# MIXR_Input_-_Instrument_Inputs.net
KiCad netlist of a schematic drawn in Altium Designer
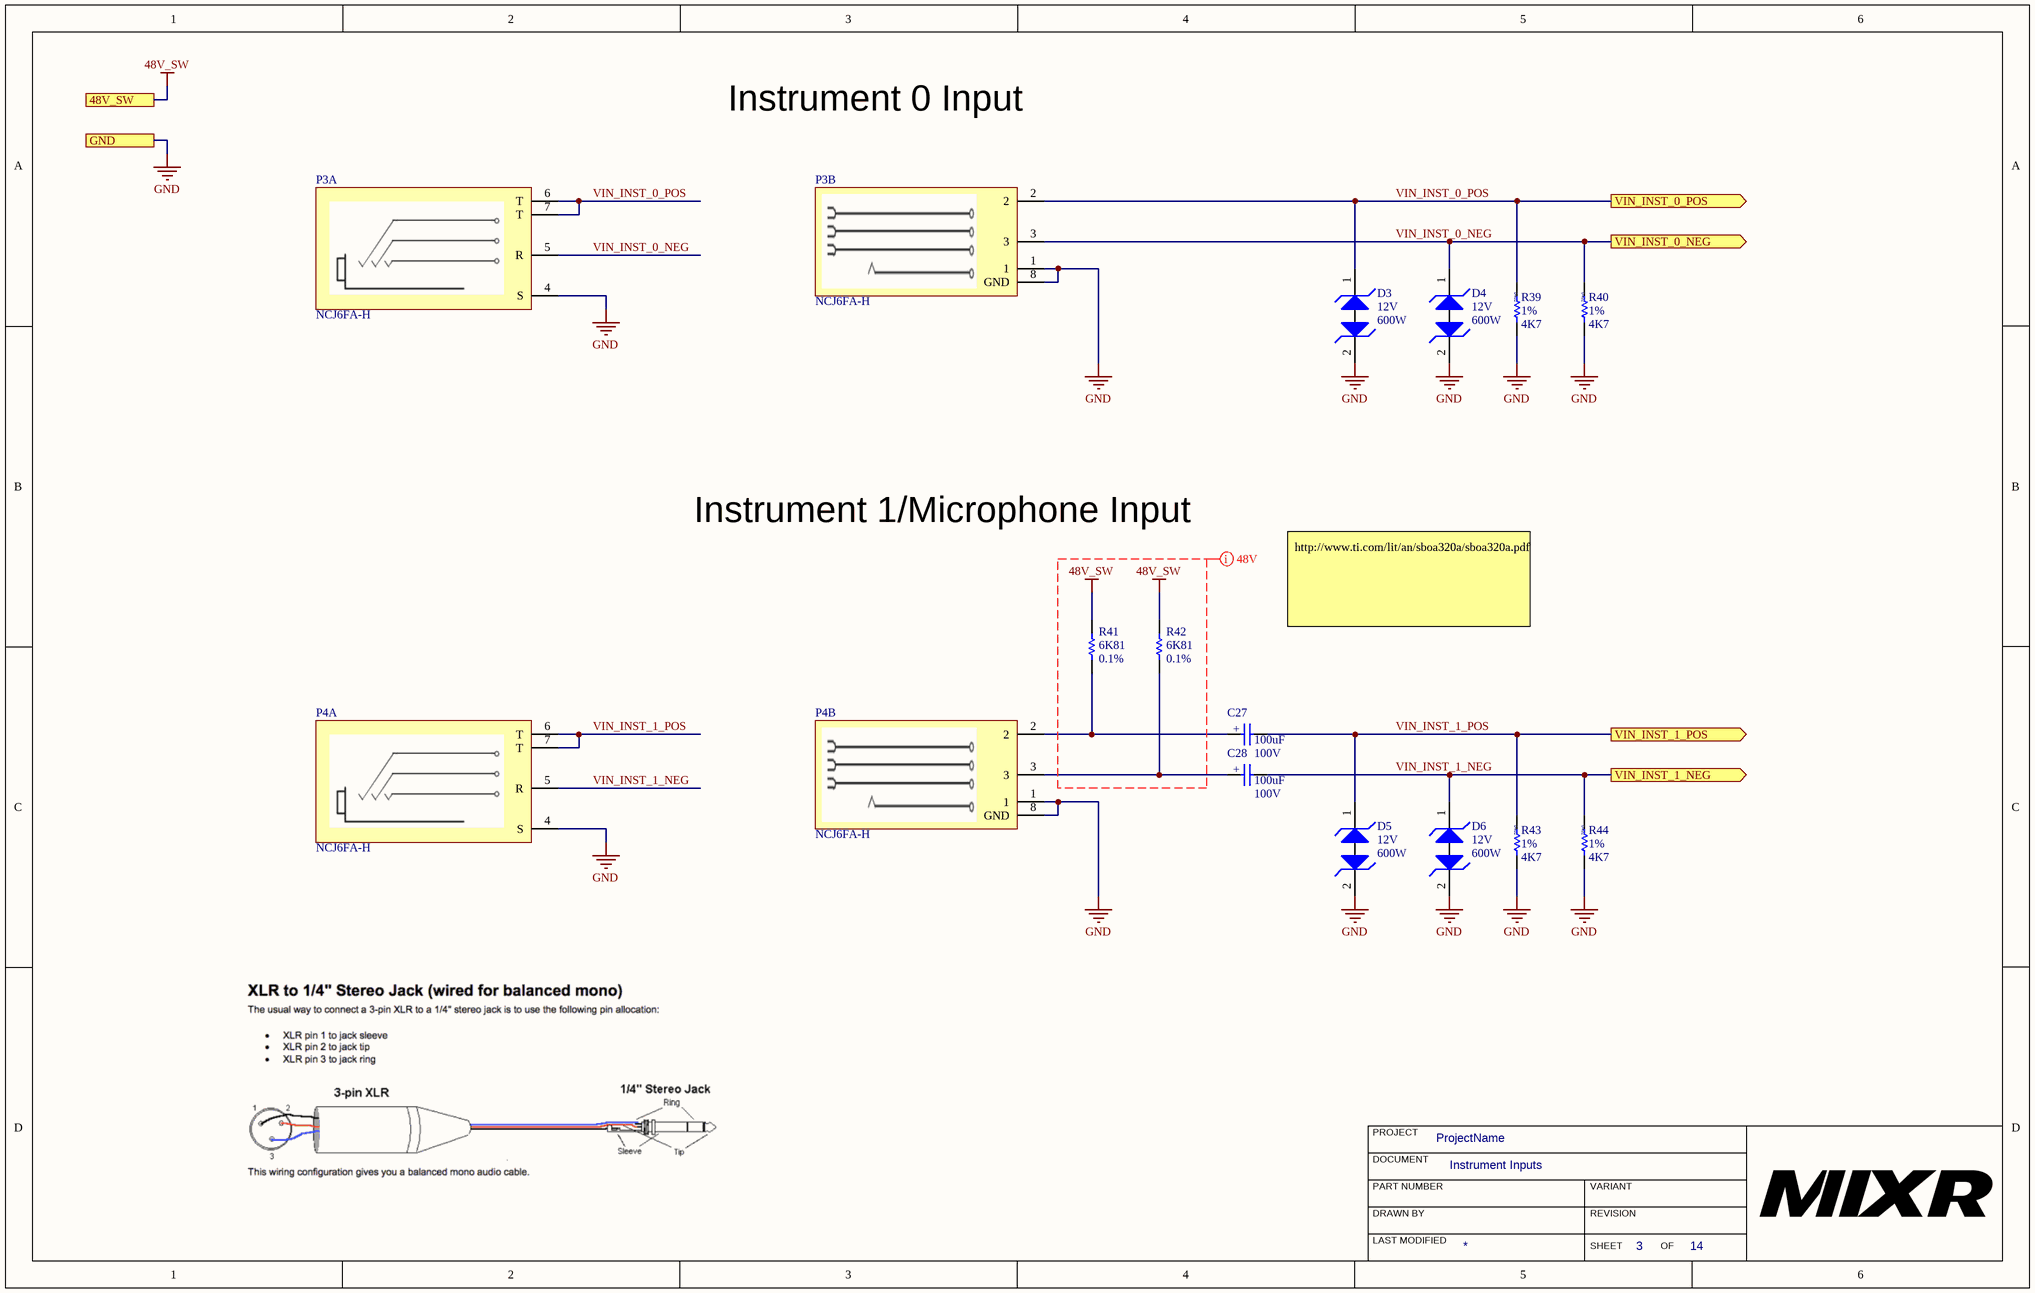
[diagram p0: MIXR Input - Instrument Inputs.SchDoc]

(export (version "E")
  (design (tool "Eeschema 10.0.6"))
  (components
    (comp (ref "C27")
      (value "CAP ALUM 100UF 20% 100V RADIAL")
      (footprint "CAP ALUM RADIAL 10x20")
      (fields
        (field (name "MANUFACTURER") "Nichicon")
        (field (name "MANUFACTURER PART NUMBER") "UFW2A101MPD1TD")
        (field (name "CAPACITANCE") "100uF")
        (field (name "TOLERANCE") "20%")
        (field (name "VOLTAGE RATING") "100V")
      )
      (libsource (lib "Schematic Diagrams") (part "CAP ALUM 100UF 20% 100V RADIAL"))
    )
    (comp (ref "C28")
      (value "CAP ALUM 100UF 20% 100V RADIAL")
      (footprint "CAP ALUM RADIAL 10x20")
      (fields
        (field (name "MANUFACTURER") "Nichicon")
        (field (name "MANUFACTURER PART NUMBER") "UFW2A101MPD1TD")
        (field (name "CAPACITANCE") "100uF")
        (field (name "TOLERANCE") "20%")
        (field (name "VOLTAGE RATING") "100V")
      )
      (libsource (lib "Schematic Diagrams") (part "CAP ALUM 100UF 20% 100V RADIAL"))
    )
    (comp (ref "D3")
      (value "DIODE TVS 12VWM 19.6VC DO-214AA (SMB)")
      (footprint "DO-214AA Diode - BI")
      (description "TVS DIODE 12V 19.6V DO214AA")
      (fields
        (field (name "MANUFACTURER") "Vishay Semiconductor Diodes Division")
        (field (name "MANUFACTURER PART NUMBER") "SMBJ12CD-M3/H")
        (field (name "VOLTAGE - REVERSE STANDOFF (TYP)") "12V")
        (field (name "POWER - PEAK PULSE") "600W")
      )
      (libsource (lib "Schematic Diagrams") (part "DIODE TVS 12VWM 19.6VC DO-214AA (SMB)"))
    )
    (comp (ref "D4")
      (value "DIODE TVS 12VWM 19.6VC DO-214AA (SMB)")
      (footprint "DO-214AA Diode - BI")
      (description "TVS DIODE 12V 19.6V DO214AA")
      (fields
        (field (name "MANUFACTURER") "Vishay Semiconductor Diodes Division")
        (field (name "MANUFACTURER PART NUMBER") "SMBJ12CD-M3/H")
        (field (name "VOLTAGE - REVERSE STANDOFF (TYP)") "12V")
        (field (name "POWER - PEAK PULSE") "600W")
      )
      (libsource (lib "Schematic Diagrams") (part "DIODE TVS 12VWM 19.6VC DO-214AA (SMB)"))
    )
    (comp (ref "D5")
      (value "DIODE TVS 12VWM 19.6VC DO-214AA (SMB)")
      (footprint "DO-214AA Diode - BI")
      (description "TVS DIODE 12V 19.6V DO214AA")
      (fields
        (field (name "MANUFACTURER") "Vishay Semiconductor Diodes Division")
        (field (name "MANUFACTURER PART NUMBER") "SMBJ12CD-M3/H")
        (field (name "VOLTAGE - REVERSE STANDOFF (TYP)") "12V")
        (field (name "POWER - PEAK PULSE") "600W")
      )
      (libsource (lib "Schematic Diagrams") (part "DIODE TVS 12VWM 19.6VC DO-214AA (SMB)"))
    )
    (comp (ref "D6")
      (value "DIODE TVS 12VWM 19.6VC DO-214AA (SMB)")
      (footprint "DO-214AA Diode - BI")
      (description "TVS DIODE 12V 19.6V DO214AA")
      (fields
        (field (name "MANUFACTURER") "Vishay Semiconductor Diodes Division")
        (field (name "MANUFACTURER PART NUMBER") "SMBJ12CD-M3/H")
        (field (name "VOLTAGE - REVERSE STANDOFF (TYP)") "12V")
        (field (name "POWER - PEAK PULSE") "600W")
      )
      (libsource (lib "Schematic Diagrams") (part "DIODE TVS 12VWM 19.6VC DO-214AA (SMB)"))
    )
    (comp (ref "P3")
      (value "CONN XLR-TRS COMBO 3 POLE")
      (footprint "CONN XLR-TRS COMBO 3 POLE")
      (description "XLR Connectors A SERIES COMBO;3POLE FEM;PCB HOR")
      (fields
        (field (name "MANUFACTURER_PART_NUMBER") "NCJ6FA-H")
        (field (name "MOUSER PART NUMBER") "568-NCJ6FA-H")
        (field (name "MANUFACTURER PART NUMBER") "NCJ6FA-H")
      )
      (libsource (lib "Schematic Diagrams") (part "CONN XLR-TRS COMBO 3 POLE"))
    )
    (comp (ref "P4")
      (value "CONN XLR-TRS COMBO 3 POLE")
      (footprint "CONN XLR-TRS COMBO 3 POLE")
      (description "XLR Connectors A SERIES COMBO;3POLE FEM;PCB HOR")
      (fields
        (field (name "MANUFACTURER_PART_NUMBER") "NCJ6FA-H")
        (field (name "MOUSER PART NUMBER") "568-NCJ6FA-H")
        (field (name "MANUFACTURER PART NUMBER") "NCJ6FA-H")
      )
      (libsource (lib "Schematic Diagrams") (part "CONN XLR-TRS COMBO 3 POLE"))
    )
    (comp (ref "R39")
      (value "RES 4.7K OHM 1% 1/10W 0402")
      (footprint "RES 0402")
      (description "YAGEO (PHYCOMP) - RC0402FR-074K7L - RES, THICK FILM, 4K7, 1%, 0.063W, 0402")
      (fields
        (field (name "MANUFACTURER") "Yageo")
        (field (name "MANUFACTURER PART NUMBER") "RC0402FR-074K7L")
        (field (name "TOLERANCE") "1%")
        (field (name "RESISTANCE") "4K7")
      )
      (libsource (lib "Schematic Diagrams") (part "RES 4.7K OHM 1% 1/10W 0402"))
    )
    (comp (ref "R40")
      (value "RES 4.7K OHM 1% 1/10W 0402")
      (footprint "RES 0402")
      (description "YAGEO (PHYCOMP) - RC0402FR-074K7L - RES, THICK FILM, 4K7, 1%, 0.063W, 0402")
      (fields
        (field (name "MANUFACTURER") "Yageo")
        (field (name "MANUFACTURER PART NUMBER") "RC0402FR-074K7L")
        (field (name "TOLERANCE") "1%")
        (field (name "RESISTANCE") "4K7")
      )
      (libsource (lib "Schematic Diagrams") (part "RES 4.7K OHM 1% 1/10W 0402"))
    )
    (comp (ref "R41")
      (value "RES 6.81k OHM 0.1% 1/10W 0603")
      (footprint "RES, 0603")
      (description "RES SMD 6.81K OHM 0.1% 1/5W 0603")
      (fields
        (field (name "MANUFACTURER") "Panasonic")
        (field (name "MANUFACTURER PART NUMBER") "ERJ-PB3B6811V")
        (field (name "TOLERANCE") "0.1%")
        (field (name "RESISTANCE") "6K81")
      )
      (libsource (lib "Schematic Diagrams") (part "RES 6.81k OHM 0.1% 1/10W 0603"))
    )
    (comp (ref "R42")
      (value "RES 6.81k OHM 0.1% 1/10W 0603")
      (footprint "RES, 0603")
      (description "RES SMD 6.81K OHM 0.1% 1/5W 0603")
      (fields
        (field (name "MANUFACTURER") "Panasonic")
        (field (name "MANUFACTURER PART NUMBER") "ERJ-PB3B6811V")
        (field (name "TOLERANCE") "0.1%")
        (field (name "RESISTANCE") "6K81")
      )
      (libsource (lib "Schematic Diagrams") (part "RES 6.81k OHM 0.1% 1/10W 0603"))
    )
    (comp (ref "R43")
      (value "RES 4.7K OHM 1% 1/10W 0402")
      (footprint "RES 0402")
      (description "YAGEO (PHYCOMP) - RC0402FR-074K7L - RES, THICK FILM, 4K7, 1%, 0.063W, 0402")
      (fields
        (field (name "MANUFACTURER") "Yageo")
        (field (name "MANUFACTURER PART NUMBER") "RC0402FR-074K7L")
        (field (name "TOLERANCE") "1%")
        (field (name "RESISTANCE") "4K7")
      )
      (libsource (lib "Schematic Diagrams") (part "RES 4.7K OHM 1% 1/10W 0402"))
    )
    (comp (ref "R44")
      (value "RES 4.7K OHM 1% 1/10W 0402")
      (footprint "RES 0402")
      (description "YAGEO (PHYCOMP) - RC0402FR-074K7L - RES, THICK FILM, 4K7, 1%, 0.063W, 0402")
      (fields
        (field (name "MANUFACTURER") "Yageo")
        (field (name "MANUFACTURER PART NUMBER") "RC0402FR-074K7L")
        (field (name "TOLERANCE") "1%")
        (field (name "RESISTANCE") "4K7")
      )
      (libsource (lib "Schematic Diagrams") (part "RES 4.7K OHM 1% 1/10W 0402"))
    )
  )
  (nets
    (net (code "1") (name "/VIN_INST_0_NEG") (class "Default")
      (node (ref "D4") (pin "1") (pinfunction "Cathode1_1") (pintype "passive"))
      (node (ref "P3") (pin "3") (pinfunction "3_3") (pintype "passive"))
      (node (ref "P3") (pin "5") (pinfunction "R_5") (pintype "passive"))
      (node (ref "R40") (pin "1") (pinfunction "1_1") (pintype "passive"))
    )
    (net (code "2") (name "/VIN_INST_0_POS") (class "Default")
      (node (ref "D3") (pin "1") (pinfunction "Cathode1_1") (pintype "passive"))
      (node (ref "P3") (pin "2") (pinfunction "2_2") (pintype "passive"))
      (node (ref "P3") (pin "6") (pinfunction "T_6") (pintype "passive"))
      (node (ref "P3") (pin "7") (pinfunction "T_7") (pintype "passive"))
      (node (ref "R39") (pin "1") (pinfunction "1_1") (pintype "passive"))
    )
    (net (code "3") (name "/VIN_INST_1_NEG") (class "Default")
      (node (ref "C28") (pin "2") (pinfunction "2_2") (pintype "passive"))
      (node (ref "D6") (pin "1") (pinfunction "Cathode1_1") (pintype "passive"))
      (node (ref "P4") (pin "5") (pinfunction "R_5") (pintype "passive"))
      (node (ref "R44") (pin "1") (pinfunction "1_1") (pintype "passive"))
    )
    (net (code "4") (name "/VIN_INST_1_POS") (class "Default")
      (node (ref "C27") (pin "2") (pinfunction "2_2") (pintype "passive"))
      (node (ref "D5") (pin "1") (pinfunction "Cathode1_1") (pintype "passive"))
      (node (ref "P4") (pin "6") (pinfunction "T_6") (pintype "passive"))
      (node (ref "P4") (pin "7") (pinfunction "T_7") (pintype "passive"))
      (node (ref "R43") (pin "1") (pinfunction "1_1") (pintype "passive"))
    )
    (net (code "5") (name "48V_SW") (class "Default")
      (node (ref "R41") (pin "1") (pinfunction "1_1") (pintype "passive"))
      (node (ref "R42") (pin "1") (pinfunction "1_1") (pintype "passive"))
    )
    (net (code "6") (name "GND") (class "Default")
      (node (ref "D3") (pin "2") (pinfunction "Cathode2_2") (pintype "passive"))
      (node (ref "D4") (pin "2") (pinfunction "Cathode2_2") (pintype "passive"))
      (node (ref "D5") (pin "2") (pinfunction "Cathode2_2") (pintype "passive"))
      (node (ref "D6") (pin "2") (pinfunction "Cathode2_2") (pintype "passive"))
      (node (ref "P3") (pin "1") (pinfunction "1_1") (pintype "passive"))
      (node (ref "P3") (pin "4") (pinfunction "S_4") (pintype "passive"))
      (node (ref "P3") (pin "8") (pinfunction "GND_8") (pintype "passive"))
      (node (ref "P4") (pin "1") (pinfunction "1_1") (pintype "passive"))
      (node (ref "P4") (pin "4") (pinfunction "S_4") (pintype "passive"))
      (node (ref "P4") (pin "8") (pinfunction "GND_8") (pintype "passive"))
      (node (ref "R39") (pin "2") (pinfunction "2_2") (pintype "passive"))
      (node (ref "R40") (pin "2") (pinfunction "2_2") (pintype "passive"))
      (node (ref "R43") (pin "2") (pinfunction "2_2") (pintype "passive"))
      (node (ref "R44") (pin "2") (pinfunction "2_2") (pintype "passive"))
    )
    (net (code "7") (name "Net-(C27-Pad1)") (class "Default")
      (node (ref "C27") (pin "1") (pinfunction "1_1") (pintype "passive"))
      (node (ref "P4") (pin "2") (pinfunction "2_2") (pintype "passive"))
      (node (ref "R41") (pin "2") (pinfunction "2_2") (pintype "passive"))
    )
    (net (code "8") (name "Net-(C28-Pad1)") (class "Default")
      (node (ref "C28") (pin "1") (pinfunction "1_1") (pintype "passive"))
      (node (ref "P4") (pin "3") (pinfunction "3_3") (pintype "passive"))
      (node (ref "R42") (pin "2") (pinfunction "2_2") (pintype "passive"))
    )
  )
)
